# starfire-core.net
KiCad netlist of a schematic drawn in EAGLE
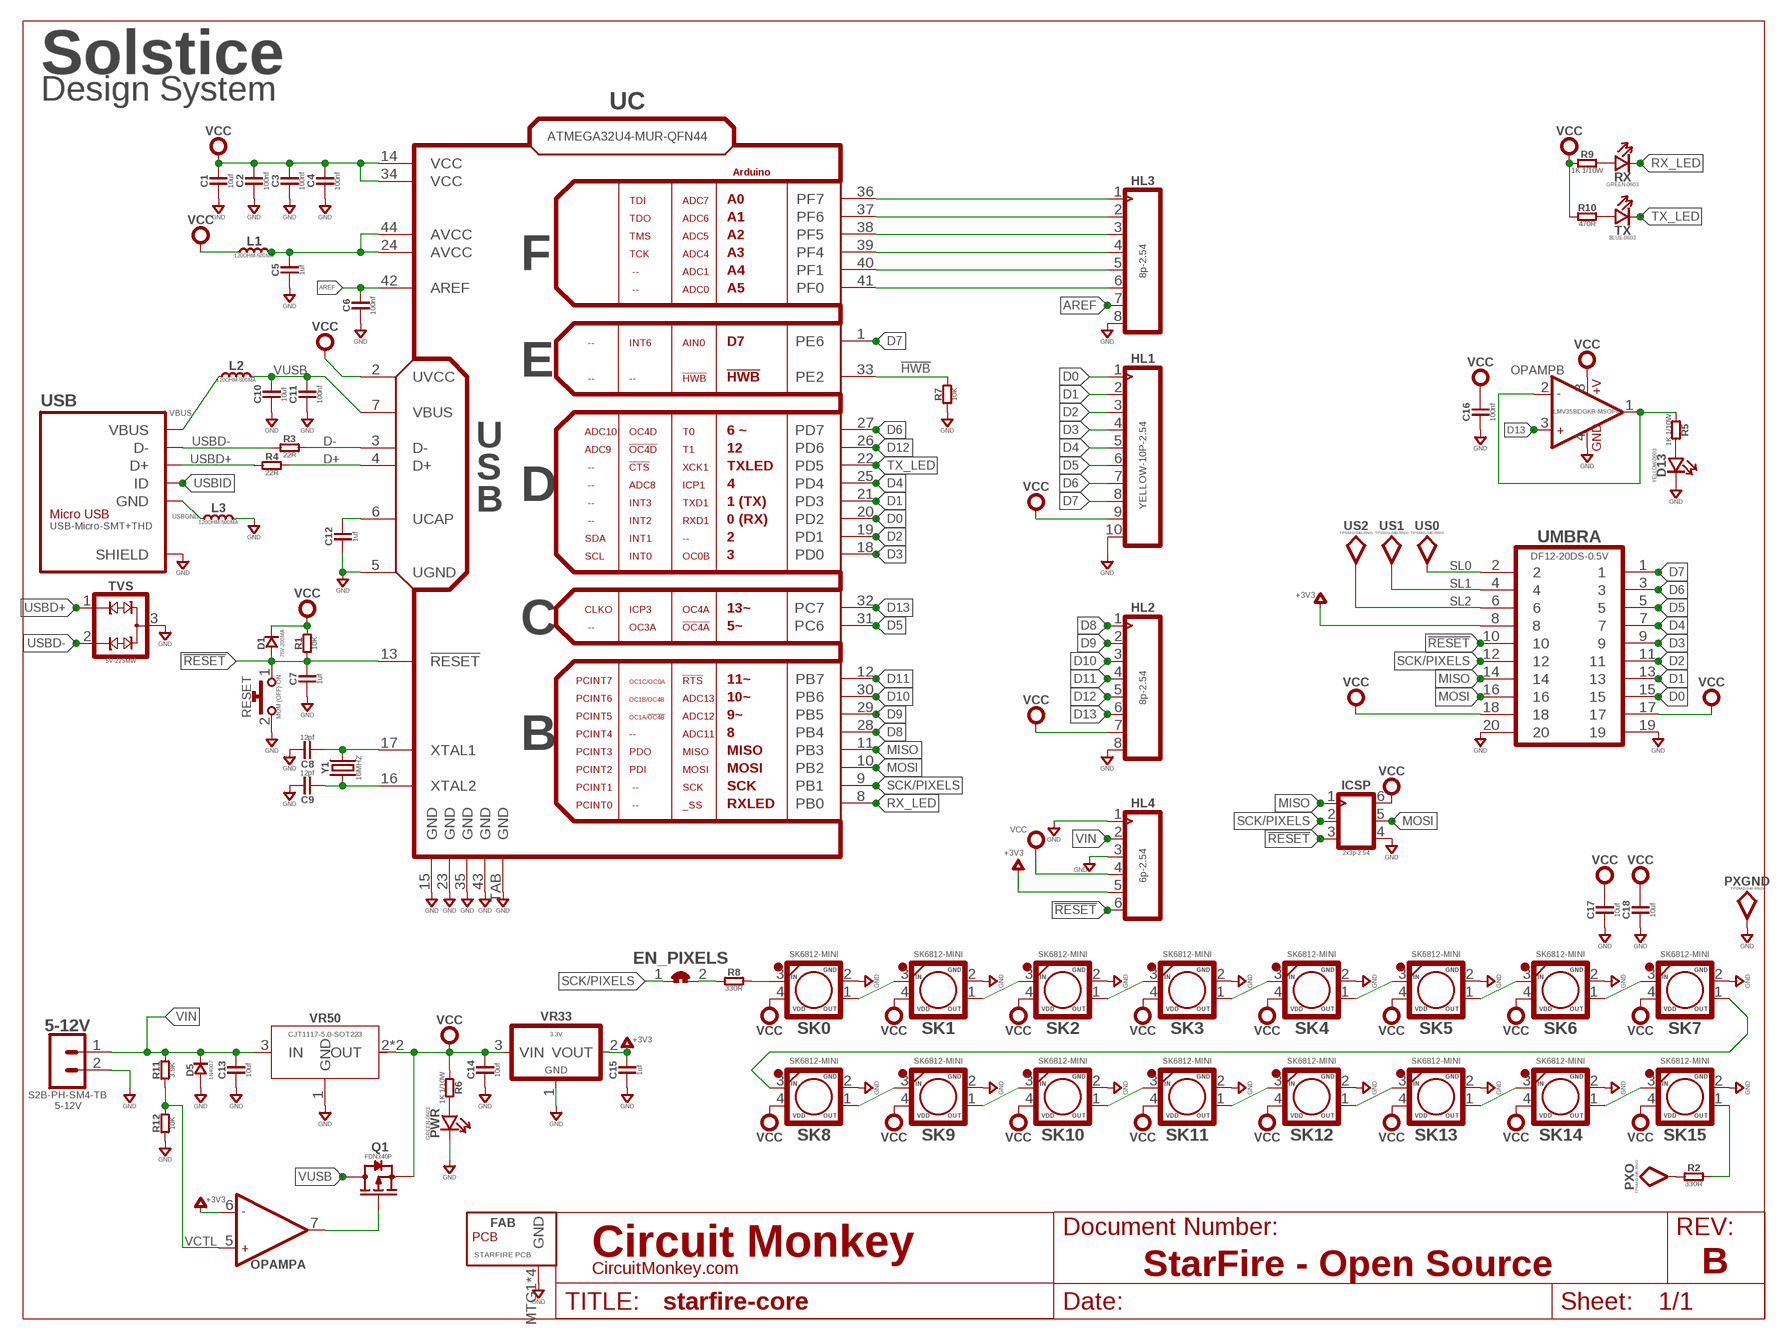
[diagram p0: schematic, sheet 1]

(export (version "E")
  (design (tool "Eeschema 10.0.6"))
  (components
    (comp (ref "5-12V")
      (value "S2B-PH-SM4-TB")
      (footprint "eagle-import:S2B-PH-SM4-")
      (libsource (lib "eagle-import") (part "02PRA-SMT"))
    )
    (comp (ref "C1")
      (value "10uf")
      (footprint "eagle-import:C0603")
      (fields (field (name "MPN") "CC0603KRX5R6BB106"))
      (libsource (lib "eagle-import") (part "CERAMIC-10UF-10V-10%-X5R(0603)"))
    )
    (comp (ref "C2")
      (value "100nf")
      (footprint "eagle-import:C0603")
      (fields (field (name "MPN") "CC0603KRX7R9BB104"))
      (libsource (lib "eagle-import") (part "CERAMIC-100NF-50V-10%-X7R(0603)"))
    )
    (comp (ref "C3")
      (value "100nf")
      (footprint "eagle-import:C0603")
      (fields (field (name "MPN") "CC0603KRX7R9BB104"))
      (libsource (lib "eagle-import") (part "CERAMIC-100NF-50V-10%-X7R(0603)"))
    )
    (comp (ref "C4")
      (value "100nf")
      (footprint "eagle-import:C0603")
      (fields (field (name "MPN") "CC0603KRX7R9BB104"))
      (libsource (lib "eagle-import") (part "CERAMIC-100NF-50V-10%-X7R(0603)"))
    )
    (comp (ref "C5")
      (value "1uf")
      (footprint "eagle-import:C0603")
      (fields (field (name "MPN") "CC0603KRX7R8BB105"))
      (libsource (lib "eagle-import") (part "CERAMIC-1UF-25V-10%-X7R(0603)"))
    )
    (comp (ref "C6")
      (value "100nf")
      (footprint "eagle-import:C0603")
      (fields (field (name "MPN") "CC0603KRX7R9BB104"))
      (libsource (lib "eagle-import") (part "CERAMIC-100NF-50V-10%-X7R(0603)"))
    )
    (comp (ref "C7")
      (value "1uf")
      (footprint "eagle-import:C0603")
      (fields (field (name "MPN") "CC0603KRX7R8BB105"))
      (libsource (lib "eagle-import") (part "CERAMIC-1UF-25V-10%-X7R(0603)"))
    )
    (comp (ref "C8")
      (value "12pf")
      (footprint "eagle-import:C0603")
      (fields (field (name "MPN") "CC0603JRNPO9BN120"))
      (libsource (lib "eagle-import") (part "CERAMIC-12PF-50V-5%-NPO(0603)"))
    )
    (comp (ref "C9")
      (value "12pf")
      (footprint "eagle-import:C0603")
      (fields (field (name "MPN") "CC0603JRNPO9BN120"))
      (libsource (lib "eagle-import") (part "CERAMIC-12PF-50V-5%-NPO(0603)"))
    )
    (comp (ref "C10")
      (value "10uf")
      (footprint "eagle-import:C0603")
      (fields (field (name "MPN") "CC0603KRX5R6BB106"))
      (libsource (lib "eagle-import") (part "CERAMIC-10UF-10V-10%-X5R(0603)"))
    )
    (comp (ref "C11")
      (value "100nf")
      (footprint "eagle-import:C0603")
      (fields (field (name "MPN") "CC0603KRX7R9BB104"))
      (libsource (lib "eagle-import") (part "CERAMIC-100NF-50V-10%-X7R(0603)"))
    )
    (comp (ref "C12")
      (value "1uf")
      (footprint "eagle-import:C0603")
      (fields (field (name "MPN") "CC0603KRX7R8BB105"))
      (libsource (lib "eagle-import") (part "CERAMIC-1UF-25V-10%-X7R(0603)"))
    )
    (comp (ref "C13")
      (value "10uf")
      (footprint "eagle-import:C0603")
      (fields (field (name "MPN") "CC0603KRX5R6BB106"))
      (libsource (lib "eagle-import") (part "CERAMIC-10UF-10V-10%-X5R(0603)"))
    )
    (comp (ref "C14")
      (value "10uf")
      (footprint "eagle-import:C0603")
      (fields (field (name "MPN") "CC0603KRX5R6BB106"))
      (libsource (lib "eagle-import") (part "CERAMIC-10UF-10V-10%-X5R(0603)"))
    )
    (comp (ref "C15")
      (value "1uf")
      (footprint "eagle-import:C0603")
      (fields (field (name "MPN") "CC0603KRX7R8BB105"))
      (libsource (lib "eagle-import") (part "CERAMIC-1UF-25V-10%-X7R(0603)"))
    )
    (comp (ref "C16")
      (value "100nf")
      (footprint "eagle-import:C0603")
      (fields (field (name "MPN") "CC0603KRX7R9BB104"))
      (libsource (lib "eagle-import") (part "CERAMIC-100NF-50V-10%-X7R(0603)"))
    )
    (comp (ref "C17")
      (value "10uf")
      (footprint "eagle-import:C0603")
      (fields (field (name "MPN") "CC0603KRX5R6BB106"))
      (libsource (lib "eagle-import") (part "CERAMIC-10UF-10V-10%-X5R(0603)"))
    )
    (comp (ref "C18")
      (value "10uf")
      (footprint "eagle-import:C0603")
      (fields (field (name "MPN") "CC0603KRX5R6BB106"))
      (libsource (lib "eagle-import") (part "CERAMIC-10UF-10V-10%-X5R(0603)"))
    )
    (comp (ref "D1")
      (value "75V-200MA")
      (footprint "eagle-import:LL-34")
      (fields (field (name "MPN") "LL4148ST"))
      (libsource (lib "eagle-import") (part "SMD-DIODE-SWITCHING-75V-200MA(LL-34)"))
    )
    (comp (ref "D5")
      (value "1N4007")
      (footprint "eagle-import:DO-214AC")
      (libsource (lib "eagle-import") (part "DIODE-GEN-PURPOSE-1KV-1A(DO-214AC)"))
    )
    (comp (ref "D13")
      (value "YELLOW-0603")
      (footprint "eagle-import:LED-0603")
      (fields (field (name "MPN") "19-217-Y5C-AM1N1VY-3T"))
      (libsource (lib "eagle-import") (part "SMD-LED-CLEAR-YELLOW(0603)"))
    )
    (comp (ref "EN_PIXELS")
      (value "SOLDER_JUMPER-80MIL-RND")
      (footprint "eagle-import:SOLDER_JUMP_80MIL_RND")
      (libsource (lib "eagle-import") (part "SOLDER_JUMPER-80MIL-RND"))
    )
    (comp (ref "FAB")
      (value "STARFIRE PCB")
      (footprint "eagle-import:PCB-BASE-B1")
      (libsource (lib "eagle-import") (part "PCB-4-MTG-BASE-B1"))
    )
    (comp (ref "HL1")
      (value "YELLOW-10P-2.54")
      (footprint "eagle-import:H10-2.54")
      (fields (field (name "MPN") "F185-1110A1BSYC1"))
      (libsource (lib "eagle-import") (part "DIP-YELLOW-FEMALE-HEADER-VERT(10P-2.54)"))
    )
    (comp (ref "HL2")
      (value "8p-2.54")
      (footprint "eagle-import:H8-2.54")
      (fields (field (name "MPN") "F185-1108A1BSYC1"))
      (libsource (lib "eagle-import") (part "DIP-BLACK-FEMALE-HEADER-VERT(8P-2.54)"))
    )
    (comp (ref "HL3")
      (value "8p-2.54")
      (footprint "eagle-import:H8-2.54")
      (fields (field (name "MPN") "F185-1108A1BSYC1"))
      (libsource (lib "eagle-import") (part "DIP-BLACK-FEMALE-HEADER-VERT(8P-2.54)"))
    )
    (comp (ref "HL4")
      (value "6p-2.54")
      (footprint "eagle-import:H6-2.54")
      (fields (field (name "MPN") "F185-1106A1BSYC1"))
      (libsource (lib "eagle-import") (part "DIP-BLACK-FEMALE-HEADER-VERT(6P-2.54)"))
    )
    (comp (ref "ICSP")
      (value "2x3p-2.54")
      (footprint "eagle-import:H2X3-2.54")
      (fields (field (name "MPN") "P125-12A1BS116A1"))
      (libsource (lib "eagle-import") (part "DIP-BLACK-MALE-HEADER(2X3P-2.54）-2.54"))
    )
    (comp (ref "L1")
      (value "120OHM-500MA")
      (footprint "eagle-import:L0603")
      (fields (field (name "MPN") "BLM18AG121SN1D"))
      (libsource (lib "eagle-import") (part "SMD-FERRITE-CHIP-120-OHM-500MA(0603)"))
    )
    (comp (ref "L2")
      (value "120OHM-500MA")
      (footprint "eagle-import:L0603")
      (fields (field (name "MPN") "BLM18AG121SN1D"))
      (libsource (lib "eagle-import") (part "SMD-FERRITE-CHIP-120-OHM-500MA(0603)"))
    )
    (comp (ref "L3")
      (value "120OHM-500MA")
      (footprint "eagle-import:L0603")
      (fields (field (name "MPN") "BLM18AG121SN1D"))
      (libsource (lib "eagle-import") (part "SMD-FERRITE-CHIP-120-OHM-500MA(0603)"))
    )
    (comp (ref "OPAMP")
      (value "LMV358IDGKR-MSOP8")
      (footprint "eagle-import:MSOP8-0.65-3X3MM")
      (fields (field (name "MPN") "LMV358IDGKR"))
      (libsource (lib "eagle-import") (part "AMPLIFIER-LMV358IDGKR(MSOP8)"))
    )
    (comp (ref "PWR")
      (value "GREEN-0603")
      (footprint "eagle-import:LED-0603")
      (fields (field (name "MPN") "19-217-G7C-AN1P2-3T"))
      (libsource (lib "eagle-import") (part "SMD-LED-CLEAR-GREEN(0603)"))
    )
    (comp (ref "PXGND")
      (value "TPSMD-040-RND")
      (footprint "eagle-import:SMD-040MIL-RND")
      (libsource (lib "eagle-import") (part "TPSMD-040-RND"))
    )
    (comp (ref "PXO")
      (value "TPSMD-040-RND")
      (footprint "eagle-import:SMD-040MIL-RND")
      (libsource (lib "eagle-import") (part "TPSMD-040-RND"))
    )
    (comp (ref "Q1")
      (value "FDN340P")
      (footprint "eagle-import:SOT-23")
      (libsource (lib "eagle-import") (part "SMD-MOSFET-P-CH-20V-2A-FDN340P(SOT-23)"))
    )
    (comp (ref "R1")
      (value "10K")
      (footprint "eagle-import:R0603")
      (fields (field (name "MPN") "RC0603FR-0710KL"))
      (libsource (lib "eagle-import") (part "SMD-RES-10K-1%-1/10W(0603)"))
    )
    (comp (ref "R2")
      (value "330R")
      (footprint "eagle-import:R0603")
      (fields (field (name "MPN") "RC0603FR-07330RL"))
      (libsource (lib "eagle-import") (part "SMD-RES-330R-1%-1/10W(0603)"))
    )
    (comp (ref "R3")
      (value "22R")
      (footprint "eagle-import:R0603")
      (fields (field (name "MPN") "RC0603JR-0722RL"))
      (libsource (lib "eagle-import") (part "SMD-RES-22R-5%-1/10W(0603)"))
    )
    (comp (ref "R4")
      (value "22R")
      (footprint "eagle-import:R0603")
      (fields (field (name "MPN") "RC0603JR-0722RL"))
      (libsource (lib "eagle-import") (part "SMD-RES-22R-5%-1/10W(0603)"))
    )
    (comp (ref "R5")
      (value "1K 1/10W")
      (footprint "eagle-import:R0603")
      (fields (field (name "MPN") "RC0603JR-071KL"))
      (libsource (lib "eagle-import") (part "SMD-RES-1K-5%-1/10W(0603)"))
    )
    (comp (ref "R6")
      (value "1K 1/10W")
      (footprint "eagle-import:R0603")
      (fields (field (name "MPN") "RC0603JR-071KL"))
      (libsource (lib "eagle-import") (part "SMD-RES-1K-5%-1/10W(0603)"))
    )
    (comp (ref "R7")
      (value "10K")
      (footprint "eagle-import:R0603")
      (fields (field (name "MPN") "RC0603FR-0710KL"))
      (libsource (lib "eagle-import") (part "SMD-RES-10K-1%-1/10W(0603)"))
    )
    (comp (ref "R8")
      (value "330R")
      (footprint "eagle-import:R0603")
      (fields (field (name "MPN") "RC0603FR-07330RL"))
      (libsource (lib "eagle-import") (part "SMD-RES-330R-1%-1/10W(0603)"))
    )
    (comp (ref "R9")
      (value "1K 1/10W")
      (footprint "eagle-import:R0603")
      (fields (field (name "MPN") "RC0603JR-071KL"))
      (libsource (lib "eagle-import") (part "SMD-RES-1K-5%-1/10W(0603)"))
    )
    (comp (ref "R10")
      (value "470R")
      (footprint "eagle-import:R0603")
      (fields (field (name "MPN") "RC0603JR-07470RL"))
      (libsource (lib "eagle-import") (part "SMD-RES-470R-5%-1/10W(0603)"))
    )
    (comp (ref "R11")
      (value "3.9K")
      (footprint "eagle-import:R0603")
      (fields (field (name "MPN") "RC0603JR-073K9L"))
      (libsource (lib "eagle-import") (part "SMD-RES-3.9K-5%-1/10W(0603)"))
    )
    (comp (ref "R12")
      (value "10K")
      (footprint "eagle-import:R0603")
      (fields (field (name "MPN") "RC0603FR-0710KL"))
      (libsource (lib "eagle-import") (part "SMD-RES-10K-1%-1/10W(0603)"))
    )
    (comp (ref "RESET")
      (value "MOM (OFF)-ON")
      (footprint "eagle-import:SWITCH-0635-2P-SMD")
      (fields (field (name "MFR") "CK Switch") (field (name "MPN") "PTS635S*SMTR"))
      (libsource (lib "eagle-import") (part "TACTILE-2PSMD"))
    )
    (comp (ref "RX")
      (value "GREEN-0603")
      (footprint "eagle-import:LED-0603")
      (fields (field (name "MPN") "19-217-G7C-AN1P2-3T"))
      (libsource (lib "eagle-import") (part "SMD-LED-CLEAR-GREEN(0603)"))
    )
    (comp (ref "SK0")
      (value "SK6812-MINI")
      (footprint "eagle-import:SMD_3535")
      (fields (field (name "MFR") "CHINA"))
      (libsource (lib "eagle-import") (part "SK6812MINI"))
    )
    (comp (ref "SK1")
      (value "SK6812-MINI")
      (footprint "eagle-import:SMD_3535")
      (fields (field (name "MFR") "CHINA"))
      (libsource (lib "eagle-import") (part "SK6812MINI"))
    )
    (comp (ref "SK2")
      (value "SK6812-MINI")
      (footprint "eagle-import:SMD_3535")
      (fields (field (name "MFR") "CHINA"))
      (libsource (lib "eagle-import") (part "SK6812MINI"))
    )
    (comp (ref "SK3")
      (value "SK6812-MINI")
      (footprint "eagle-import:SMD_3535")
      (fields (field (name "MFR") "CHINA"))
      (libsource (lib "eagle-import") (part "SK6812MINI"))
    )
    (comp (ref "SK4")
      (value "SK6812-MINI")
      (footprint "eagle-import:SMD_3535")
      (fields (field (name "MFR") "CHINA"))
      (libsource (lib "eagle-import") (part "SK6812MINI"))
    )
    (comp (ref "SK5")
      (value "SK6812-MINI")
      (footprint "eagle-import:SMD_3535")
      (fields (field (name "MFR") "CHINA"))
      (libsource (lib "eagle-import") (part "SK6812MINI"))
    )
    (comp (ref "SK6")
      (value "SK6812-MINI")
      (footprint "eagle-import:SMD_3535")
      (fields (field (name "MFR") "CHINA"))
      (libsource (lib "eagle-import") (part "SK6812MINI"))
    )
    (comp (ref "SK7")
      (value "SK6812-MINI")
      (footprint "eagle-import:SMD_3535")
      (fields (field (name "MFR") "CHINA"))
      (libsource (lib "eagle-import") (part "SK6812MINI"))
    )
    (comp (ref "SK8")
      (value "SK6812-MINI")
      (footprint "eagle-import:SMD_3535")
      (fields (field (name "MFR") "CHINA"))
      (libsource (lib "eagle-import") (part "SK6812MINI"))
    )
    (comp (ref "SK9")
      (value "SK6812-MINI")
      (footprint "eagle-import:SMD_3535")
      (fields (field (name "MFR") "CHINA"))
      (libsource (lib "eagle-import") (part "SK6812MINI"))
    )
    (comp (ref "SK10")
      (value "SK6812-MINI")
      (footprint "eagle-import:SMD_3535")
      (fields (field (name "MFR") "CHINA"))
      (libsource (lib "eagle-import") (part "SK6812MINI"))
    )
    (comp (ref "SK11")
      (value "SK6812-MINI")
      (footprint "eagle-import:SMD_3535")
      (fields (field (name "MFR") "CHINA"))
      (libsource (lib "eagle-import") (part "SK6812MINI"))
    )
    (comp (ref "SK12")
      (value "SK6812-MINI")
      (footprint "eagle-import:SMD_3535")
      (fields (field (name "MFR") "CHINA"))
      (libsource (lib "eagle-import") (part "SK6812MINI"))
    )
    (comp (ref "SK13")
      (value "SK6812-MINI")
      (footprint "eagle-import:SMD_3535")
      (fields (field (name "MFR") "CHINA"))
      (libsource (lib "eagle-import") (part "SK6812MINI"))
    )
    (comp (ref "SK14")
      (value "SK6812-MINI")
      (footprint "eagle-import:SMD_3535")
      (fields (field (name "MFR") "CHINA"))
      (libsource (lib "eagle-import") (part "SK6812MINI"))
    )
    (comp (ref "SK15")
      (value "SK6812-MINI")
      (footprint "eagle-import:SMD_3535")
      (fields (field (name "MFR") "CHINA"))
      (libsource (lib "eagle-import") (part "SK6812MINI"))
    )
    (comp (ref "TVS")
      (value "5V-225MW")
      (footprint "eagle-import:SOT-23")
      (fields (field (name "MPN") "CESD5V0AP"))
      (libsource (lib "eagle-import") (part "SMD-DIODE-TVS-5V-225MW(SOT-23)"))
    )
    (comp (ref "TX")
      (value "BLUE-0603")
      (footprint "eagle-import:LED-0603")
      (fields (field (name "MPN") "19-217-BHC-ZL1M2RY-3T"))
      (libsource (lib "eagle-import") (part "SMD-LED-CLEAR-BLUE(0603)"))
    )
    (comp (ref "UC")
      (value "ATMEGA32U4-MUR-QFN44")
      (footprint "eagle-import:QFN44G-0.5-7X7MM")
      (fields (field (name "MPN") "ATMEGA32U4-MUR"))
      (libsource (lib "eagle-import") (part "MCU-ATMEGA32U4-MUR(VQFN44)"))
    )
    (comp (ref "UMBRA")
      (value "DF12-20DS-0.5V")
      (footprint "eagle-import:DF12-20P-RCPT-MTL-BOSS")
      (libsource (lib "eagle-import") (part "DF12-20P-RCPT"))
    )
    (comp (ref "US0")
      (value "TPSMD-040-RND")
      (footprint "eagle-import:SMD-040MIL-RND")
      (libsource (lib "eagle-import") (part "TPSMD-040-RND"))
    )
    (comp (ref "US1")
      (value "TPSMD-040-RND")
      (footprint "eagle-import:SMD-040MIL-RND")
      (libsource (lib "eagle-import") (part "TPSMD-040-RND"))
    )
    (comp (ref "US2")
      (value "TPSMD-040-RND")
      (footprint "eagle-import:SMD-040MIL-RND")
      (libsource (lib "eagle-import") (part "TPSMD-040-RND"))
    )
    (comp (ref "USB")
      (value "USB-Micro-SMT+THD")
      (footprint "eagle-import:MICRO-USB5+6P-SMD-0.65-AB")
      (fields (field (name "MPN") "ZX62-B-5PA8"))
      (libsource (lib "eagle-import") (part "MICRO-USB-SMD(ZX62-B-5PA)"))
    )
    (comp (ref "VR33")
      (value "3.3V")
      (footprint "eagle-import:SOT-23")
      (fields (field (name "MPN") "XC6206P332MR-G"))
      (libsource (lib "eagle-import") (part "PMIC-LDO-XC6206P332MR-G(SOT23)"))
    )
    (comp (ref "VR50")
      (value "CJT1117-5.0-SOT223")
      (footprint "eagle-import:SOT-223")
      (fields (field (name "MPN") "CJT1117-5.0"))
      (libsource (lib "eagle-import") (part "PMIC-CJT1117-5.0(SOT223)"))
    )
    (comp (ref "Y1")
      (value "16MHZ")
      (footprint "eagle-import:X2-SMD-5.0X3.2X1.3MM")
      (fields (field (name "MPN") "X053201602002"))
      (libsource (lib "eagle-import") (part "SMD-CRYSTAL-16MHZ-8PF-20PPM-40R(2P-5.0X3.2MM)"))
    )
  )
  (nets
    (net (code "1") (name "+3V3") (class "Default")
      (node (ref "C15") (pin "2") (pinfunction "2_2") (pintype "passive"))
      (node (ref "HL4") (pin "5") (pinfunction "5_5") (pintype "bidirectional"))
      (node (ref "OPAMP") (pin "6") (pinfunction "-IN2_6") (pintype "input"))
      (node (ref "UMBRA") (pin "8") (pinfunction "8_8") (pintype "bidirectional"))
      (node (ref "VR33") (pin "2") (pinfunction "VOUT_2") (pintype "output"))
    )
    (net (code "2") (name "/D+") (class "Default")
      (node (ref "R4") (pin "2") (pinfunction "2_2") (pintype "passive"))
      (node (ref "UC") (pin "4") (pinfunction "D+_4") (pintype "bidirectional"))
    )
    (net (code "3") (name "/D-") (class "Default")
      (node (ref "R3") (pin "2") (pinfunction "2_2") (pintype "passive"))
      (node (ref "UC") (pin "3") (pinfunction "D-_3") (pintype "bidirectional"))
    )
    (net (code "4") (name "/SL0") (class "Default")
      (node (ref "UMBRA") (pin "2") (pinfunction "2_2") (pintype "bidirectional"))
      (node (ref "US0") (pin "TP") (pinfunction "P$1_TP") (pintype "bidirectional"))
    )
    (net (code "5") (name "/SL1") (class "Default")
      (node (ref "UMBRA") (pin "4") (pinfunction "4_4") (pintype "bidirectional"))
      (node (ref "US1") (pin "TP") (pinfunction "P$1_TP") (pintype "bidirectional"))
    )
    (net (code "6") (name "/SL2") (class "Default")
      (node (ref "UMBRA") (pin "6") (pinfunction "6_6") (pintype "bidirectional"))
      (node (ref "US2") (pin "TP") (pinfunction "P$1_TP") (pintype "bidirectional"))
    )
    (net (code "7") (name "/USBGND") (class "Default")
      (node (ref "L3") (pin "1") (pinfunction "1_1") (pintype "passive"))
      (node (ref "USB") (pin "5") (pinfunction "GND_5") (pintype "power_in"))
    )
    (net (code "8") (name "/VBUS") (class "Default")
      (node (ref "L2") (pin "1") (pinfunction "1_1") (pintype "passive"))
      (node (ref "USB") (pin "1") (pinfunction "VBUS_1") (pintype "power_in"))
    )
    (net (code "9") (name "/VCTL") (class "Default")
      (node (ref "OPAMP") (pin "5") (pinfunction "+IN2_5") (pintype "input"))
      (node (ref "R11") (pin "1") (pinfunction "1_1") (pintype "passive"))
      (node (ref "R12") (pin "2") (pinfunction "2_2") (pintype "passive"))
    )
    (net (code "10") (name "/~{HWB}") (class "Default")
      (node (ref "R7") (pin "2") (pinfunction "2_2") (pintype "passive"))
      (node (ref "UC") (pin "33") (pinfunction "PE2_33") (pintype "bidirectional"))
    )
    (net (code "11") (name "/~{RESET}") (class "Default")
      (node (ref "C7") (pin "2") (pinfunction "2_2") (pintype "passive"))
      (node (ref "D1") (pin "A") (pinfunction "+_A") (pintype "passive"))
      (node (ref "HL4") (pin "6") (pinfunction "6_6") (pintype "bidirectional"))
      (node (ref "ICSP") (pin "3") (pinfunction "3_3") (pintype "bidirectional"))
      (node (ref "R1") (pin "1") (pinfunction "1_1") (pintype "passive"))
      (node (ref "RESET") (pin "1") (pinfunction "1_1") (pintype "bidirectional"))
      (node (ref "UC") (pin "13") (pinfunction "~{RESET}_13") (pintype "input"))
      (node (ref "UMBRA") (pin "10") (pinfunction "10_10") (pintype "bidirectional"))
    )
    (net (code "12") (name "AREF") (class "Default")
      (node (ref "C6") (pin "2") (pinfunction "2_2") (pintype "passive"))
      (node (ref "HL3") (pin "7") (pinfunction "7_7") (pintype "bidirectional"))
      (node (ref "UC") (pin "42") (pinfunction "AREF_42") (pintype "input"))
    )
    (net (code "13") (name "D0") (class "Default")
      (node (ref "HL1") (pin "1") (pinfunction "1_1") (pintype "bidirectional"))
      (node (ref "UC") (pin "20") (pinfunction "PD2_20") (pintype "bidirectional"))
      (node (ref "UMBRA") (pin "15") (pinfunction "15_15") (pintype "bidirectional"))
    )
    (net (code "14") (name "D1") (class "Default")
      (node (ref "HL1") (pin "2") (pinfunction "2_2") (pintype "bidirectional"))
      (node (ref "UC") (pin "21") (pinfunction "PD3_21") (pintype "bidirectional"))
      (node (ref "UMBRA") (pin "13") (pinfunction "13_13") (pintype "bidirectional"))
    )
    (net (code "15") (name "D2") (class "Default")
      (node (ref "HL1") (pin "3") (pinfunction "3_3") (pintype "bidirectional"))
      (node (ref "UC") (pin "19") (pinfunction "PD1_19") (pintype "bidirectional"))
      (node (ref "UMBRA") (pin "11") (pinfunction "11_11") (pintype "bidirectional"))
    )
    (net (code "16") (name "D3") (class "Default")
      (node (ref "HL1") (pin "4") (pinfunction "4_4") (pintype "bidirectional"))
      (node (ref "UC") (pin "18") (pinfunction "PD0_18") (pintype "bidirectional"))
      (node (ref "UMBRA") (pin "9") (pinfunction "9_9") (pintype "bidirectional"))
    )
    (net (code "17") (name "D4") (class "Default")
      (node (ref "HL1") (pin "5") (pinfunction "5_5") (pintype "bidirectional"))
      (node (ref "UC") (pin "25") (pinfunction "PD4_25") (pintype "bidirectional"))
      (node (ref "UMBRA") (pin "7") (pinfunction "7_7") (pintype "bidirectional"))
    )
    (net (code "18") (name "D5") (class "Default")
      (node (ref "HL1") (pin "6") (pinfunction "6_6") (pintype "bidirectional"))
      (node (ref "UC") (pin "31") (pinfunction "PC6_31") (pintype "bidirectional"))
      (node (ref "UMBRA") (pin "5") (pinfunction "5_5") (pintype "bidirectional"))
    )
    (net (code "19") (name "D6") (class "Default")
      (node (ref "HL1") (pin "7") (pinfunction "7_7") (pintype "bidirectional"))
      (node (ref "UC") (pin "27") (pinfunction "PD7_27") (pintype "bidirectional"))
      (node (ref "UMBRA") (pin "3") (pinfunction "3_3") (pintype "bidirectional"))
    )
    (net (code "20") (name "D7") (class "Default")
      (node (ref "HL1") (pin "8") (pinfunction "8_8") (pintype "bidirectional"))
      (node (ref "UC") (pin "1") (pinfunction "PE6_1") (pintype "bidirectional"))
      (node (ref "UMBRA") (pin "1") (pinfunction "1_1") (pintype "bidirectional"))
    )
    (net (code "21") (name "D8") (class "Default")
      (node (ref "HL2") (pin "1") (pinfunction "1_1") (pintype "bidirectional"))
      (node (ref "UC") (pin "28") (pinfunction "PB4_28") (pintype "bidirectional"))
    )
    (net (code "22") (name "D9") (class "Default")
      (node (ref "HL2") (pin "2") (pinfunction "2_2") (pintype "bidirectional"))
      (node (ref "UC") (pin "29") (pinfunction "PB5_29") (pintype "bidirectional"))
    )
    (net (code "23") (name "D10") (class "Default")
      (node (ref "HL2") (pin "3") (pinfunction "3_3") (pintype "bidirectional"))
      (node (ref "UC") (pin "30") (pinfunction "PB6_30") (pintype "bidirectional"))
    )
    (net (code "24") (name "D11") (class "Default")
      (node (ref "HL2") (pin "4") (pinfunction "4_4") (pintype "bidirectional"))
      (node (ref "UC") (pin "12") (pinfunction "PB7_12") (pintype "bidirectional"))
    )
    (net (code "25") (name "D12") (class "Default")
      (node (ref "HL2") (pin "5") (pinfunction "5_5") (pintype "bidirectional"))
      (node (ref "UC") (pin "26") (pinfunction "PD6_26") (pintype "bidirectional"))
    )
    (net (code "26") (name "D13") (class "Default")
      (node (ref "HL2") (pin "6") (pinfunction "6_6") (pintype "bidirectional"))
      (node (ref "OPAMP") (pin "3") (pinfunction "+IN1_3") (pintype "input"))
      (node (ref "UC") (pin "32") (pinfunction "PC7_32") (pintype "bidirectional"))
    )
    (net (code "27") (name "GND") (class "Default")
      (node (ref "5-12V") (pin "2") (pinfunction "2_2") (pintype "passive"))
      (node (ref "C1") (pin "1") (pinfunction "1_1") (pintype "passive"))
      (node (ref "C10") (pin "1") (pinfunction "1_1") (pintype "passive"))
      (node (ref "C11") (pin "1") (pinfunction "1_1") (pintype "passive"))
      (node (ref "C12") (pin "1") (pinfunction "1_1") (pintype "passive"))
      (node (ref "C13") (pin "1") (pinfunction "1_1") (pintype "passive"))
      (node (ref "C14") (pin "1") (pinfunction "1_1") (pintype "passive"))
      (node (ref "C15") (pin "1") (pinfunction "1_1") (pintype "passive"))
      (node (ref "C16") (pin "1") (pinfunction "1_1") (pintype "passive"))
      (node (ref "C17") (pin "1") (pinfunction "1_1") (pintype "passive"))
      (node (ref "C18") (pin "1") (pinfunction "1_1") (pintype "passive"))
      (node (ref "C2") (pin "1") (pinfunction "1_1") (pintype "passive"))
      (node (ref "C3") (pin "1") (pinfunction "1_1") (pintype "passive"))
      (node (ref "C4") (pin "1") (pinfunction "1_1") (pintype "passive"))
      (node (ref "C5") (pin "1") (pinfunction "1_1") (pintype "passive"))
      (node (ref "C6") (pin "1") (pinfunction "1_1") (pintype "passive"))
      (node (ref "C7") (pin "1") (pinfunction "1_1") (pintype "passive"))
      (node (ref "C8") (pin "2") (pinfunction "2_2") (pintype "passive"))
      (node (ref "C9") (pin "2") (pinfunction "2_2") (pintype "passive"))
      (node (ref "D13") (pin "-") (pinfunction "-_-") (pintype "passive"))
      (node (ref "D5") (pin "1") (pinfunction "+_1") (pintype "passive"))
      (node (ref "FAB") (pin "MTG1") (pinfunction "GND_MTG1") (pintype "bidirectional"))
      (node (ref "FAB") (pin "MTG2") (pinfunction "GND_MTG2") (pintype "bidirectional"))
      (node (ref "FAB") (pin "MTG3") (pinfunction "GND_MTG3") (pintype "bidirectional"))
      (node (ref "FAB") (pin "MTG4") (pinfunction "GND_MTG4") (pintype "bidirectional"))
      (node (ref "HL1") (pin "10") (pinfunction "10_10") (pintype "bidirectional"))
      (node (ref "HL2") (pin "8") (pinfunction "8_8") (pintype "bidirectional"))
      (node (ref "HL3") (pin "8") (pinfunction "8_8") (pintype "bidirectional"))
      (node (ref "HL4") (pin "1") (pinfunction "1_1") (pintype "bidirectional"))
      (node (ref "HL4") (pin "3") (pinfunction "3_3") (pintype "bidirectional"))
      (node (ref "ICSP") (pin "4") (pinfunction "4_4") (pintype "bidirectional"))
      (node (ref "L3") (pin "2") (pinfunction "2_2") (pintype "passive"))
      (node (ref "OPAMP") (pin "4") (pinfunction "GND_4") (pintype "power_in"))
      (node (ref "PWR") (pin "-") (pinfunction "-_-") (pintype "passive"))
      (node (ref "PXGND") (pin "TP") (pinfunction "P$1_TP") (pintype "bidirectional"))
      (node (ref "R12") (pin "1") (pinfunction "1_1") (pintype "passive"))
      (node (ref "R7") (pin "1") (pinfunction "1_1") (pintype "passive"))
      (node (ref "RESET") (pin "2") (pinfunction "2_2") (pintype "bidirectional"))
      (node (ref "SK0") (pin "2") (pinfunction "GND_2") (pintype "bidirectional"))
      (node (ref "SK1") (pin "2") (pinfunction "GND_2") (pintype "bidirectional"))
      (node (ref "SK10") (pin "2") (pinfunction "GND_2") (pintype "bidirectional"))
      (node (ref "SK11") (pin "2") (pinfunction "GND_2") (pintype "bidirectional"))
      (node (ref "SK12") (pin "2") (pinfunction "GND_2") (pintype "bidirectional"))
      (node (ref "SK13") (pin "2") (pinfunction "GND_2") (pintype "bidirectional"))
      (node (ref "SK14") (pin "2") (pinfunction "GND_2") (pintype "bidirectional"))
      (node (ref "SK15") (pin "2") (pinfunction "GND_2") (pintype "bidirectional"))
      (node (ref "SK2") (pin "2") (pinfunction "GND_2") (pintype "bidirectional"))
      (node (ref "SK3") (pin "2") (pinfunction "GND_2") (pintype "bidirectional"))
      (node (ref "SK4") (pin "2") (pinfunction "GND_2") (pintype "bidirectional"))
      (node (ref "SK5") (pin "2") (pinfunction "GND_2") (pintype "bidirectional"))
      (node (ref "SK6") (pin "2") (pinfunction "GND_2") (pintype "bidirectional"))
      (node (ref "SK7") (pin "2") (pinfunction "GND_2") (pintype "bidirectional"))
      (node (ref "SK8") (pin "2") (pinfunction "GND_2") (pintype "bidirectional"))
      (node (ref "SK9") (pin "2") (pinfunction "GND_2") (pintype "bidirectional"))
      (node (ref "TVS") (pin "3") (pinfunction "3_3") (pintype "bidirectional"))
      (node (ref "UC") (pin "15") (pinfunction "GND_15") (pintype "power_in"))
      (node (ref "UC") (pin "23") (pinfunction "GND_23") (pintype "power_in"))
      (node (ref "UC") (pin "35") (pinfunction "GND_35") (pintype "power_in"))
      (node (ref "UC") (pin "43") (pinfunction "GND_43") (pintype "power_in"))
      (node (ref "UC") (pin "5") (pinfunction "UGND_5") (pintype "bidirectional"))
      (node (ref "UC") (pin "TAB") (pinfunction "GND_TAB") (pintype "power_in"))
      (node (ref "UMBRA") (pin "19") (pinfunction "19_19") (pintype "bidirectional"))
      (node (ref "UMBRA") (pin "20") (pinfunction "20_20") (pintype "bidirectional"))
      (node (ref "USB") (pin "P1") (pinfunction "SHIELD_P1") (pintype "power_in"))
      (node (ref "USB") (pin "P2") (pinfunction "SHIELD_P2") (pintype "power_in"))
      (node (ref "USB") (pin "P3_1") (pinfunction "SHIELD_P3_1") (pintype "power_in"))
      (node (ref "USB") (pin "P3_2") (pinfunction "SHIELD_P3_2") (pintype "power_in"))
      (node (ref "USB") (pin "P3_3") (pinfunction "SHIELD_P3_3") (pintype "power_in"))
      (node (ref "USB") (pin "P4_1") (pinfunction "SHIELD_P4_1") (pintype "power_in"))
      (node (ref "USB") (pin "P4_2") (pinfunction "SHIELD_P4_2") (pintype "power_in"))
      (node (ref "USB") (pin "P4_3") (pinfunction "SHIELD_P4_3") (pintype "power_in"))
      (node (ref "USB") (pin "P5") (pinfunction "SHIELD_P5") (pintype "power_in"))
      (node (ref "USB") (pin "P6") (pinfunction "SHIELD_P6") (pintype "power_in"))
      (node (ref "VR33") (pin "1") (pinfunction "VSS_1") (pintype "power_in"))
      (node (ref "VR50") (pin "1") (pinfunction "GND_1") (pintype "bidirectional"))
    )
    (net (code "28") (name "MISO") (class "Default")
      (node (ref "ICSP") (pin "1") (pinfunction "1_1") (pintype "bidirectional"))
      (node (ref "UC") (pin "11") (pinfunction "PB3_11") (pintype "bidirectional"))
      (node (ref "UMBRA") (pin "14") (pinfunction "14_14") (pintype "bidirectional"))
    )
    (net (code "29") (name "MOSI") (class "Default")
      (node (ref "ICSP") (pin "5") (pinfunction "5_5") (pintype "bidirectional"))
      (node (ref "UC") (pin "10") (pinfunction "PB2_10") (pintype "bidirectional"))
      (node (ref "UMBRA") (pin "16") (pinfunction "16_16") (pintype "bidirectional"))
    )
    (net (code "30") (name "Net-(C5-Pad2)") (class "Default")
      (node (ref "C5") (pin "2") (pinfunction "2_2") (pintype "passive"))
      (node (ref "L1") (pin "2") (pinfunction "2_2") (pintype "passive"))
      (node (ref "UC") (pin "24") (pinfunction "AVCC_24") (pintype "power_in"))
      (node (ref "UC") (pin "44") (pinfunction "AVCC_44") (pintype "power_in"))
    )
    (net (code "31") (name "Net-(D13-Pad+)") (class "Default")
      (node (ref "D13") (pin "+") (pinfunction "+_+") (pintype "passive"))
      (node (ref "R5") (pin "2") (pinfunction "2_2") (pintype "passive"))
    )
    (net (code "32") (name "Net-(EN_PIXELS-P$2)") (class "Default")
      (node (ref "EN_PIXELS") (pin "2") (pinfunction "P$2_2") (pintype "passive"))
      (node (ref "R8") (pin "1") (pinfunction "1_1") (pintype "passive"))
    )
    (net (code "33") (name "Net-(OPAMPA-OUT2)") (class "Default")
      (node (ref "OPAMP") (pin "7") (pinfunction "OUT2_7") (pintype "output"))
      (node (ref "Q1") (pin "1") (pinfunction "G_1") (pintype "passive"))
    )
    (net (code "34") (name "Net-(OPAMPB--IN1)") (class "Default")
      (node (ref "OPAMP") (pin "1") (pinfunction "OUT1_1") (pintype "output"))
      (node (ref "OPAMP") (pin "2") (pinfunction "-IN1_2") (pintype "input"))
      (node (ref "R5") (pin "1") (pinfunction "1_1") (pintype "passive"))
    )
    (net (code "35") (name "Net-(PWR-Pad+)") (class "Default")
      (node (ref "PWR") (pin "+") (pinfunction "+_+") (pintype "passive"))
      (node (ref "R6") (pin "2") (pinfunction "2_2") (pintype "passive"))
    )
    (net (code "36") (name "Net-(PXO-P$1)") (class "Default")
      (node (ref "PXO") (pin "TP") (pinfunction "P$1_TP") (pintype "bidirectional"))
      (node (ref "R2") (pin "1") (pinfunction "1_1") (pintype "passive"))
    )
    (net (code "37") (name "Net-(R9-Pad2)") (class "Default")
      (node (ref "R9") (pin "2") (pinfunction "2_2") (pintype "passive"))
      (node (ref "RX") (pin "+") (pinfunction "+_+") (pintype "passive"))
    )
    (net (code "38") (name "Net-(R10-Pad2)") (class "Default")
      (node (ref "R10") (pin "2") (pinfunction "2_2") (pintype "passive"))
      (node (ref "TX") (pin "+") (pinfunction "+_+") (pintype "passive"))
    )
    (net (code "39") (name "Net-(SK0-IN)") (class "Default")
      (node (ref "R8") (pin "2") (pinfunction "2_2") (pintype "passive"))
      (node (ref "SK0") (pin "3") (pinfunction "IN_3") (pintype "bidirectional"))
    )
    (net (code "40") (name "Net-(SK0-OUT)") (class "Default")
      (node (ref "SK0") (pin "1") (pinfunction "OUT_1") (pintype "bidirectional"))
      (node (ref "SK1") (pin "3") (pinfunction "IN_3") (pintype "bidirectional"))
    )
    (net (code "41") (name "Net-(SK1-OUT)") (class "Default")
      (node (ref "SK1") (pin "1") (pinfunction "OUT_1") (pintype "bidirectional"))
      (node (ref "SK2") (pin "3") (pinfunction "IN_3") (pintype "bidirectional"))
    )
    (net (code "42") (name "Net-(SK2-OUT)") (class "Default")
      (node (ref "SK2") (pin "1") (pinfunction "OUT_1") (pintype "bidirectional"))
      (node (ref "SK3") (pin "3") (pinfunction "IN_3") (pintype "bidirectional"))
    )
    (net (code "43") (name "Net-(SK3-OUT)") (class "Default")
      (node (ref "SK3") (pin "1") (pinfunction "OUT_1") (pintype "bidirectional"))
      (node (ref "SK4") (pin "3") (pinfunction "IN_3") (pintype "bidirectional"))
    )
    (net (code "44") (name "Net-(SK4-OUT)") (class "Default")
      (node (ref "SK4") (pin "1") (pinfunction "OUT_1") (pintype "bidirectional"))
      (node (ref "SK5") (pin "3") (pinfunction "IN_3") (pintype "bidirectional"))
    )
    (net (code "45") (name "Net-(SK5-OUT)") (class "Default")
      (node (ref "SK5") (pin "1") (pinfunction "OUT_1") (pintype "bidirectional"))
      (node (ref "SK6") (pin "3") (pinfunction "IN_3") (pintype "bidirectional"))
    )
    (net (code "46") (name "Net-(SK6-OUT)") (class "Default")
      (node (ref "SK6") (pin "1") (pinfunction "OUT_1") (pintype "bidirectional"))
      (node (ref "SK7") (pin "3") (pinfunction "IN_3") (pintype "bidirectional"))
    )
    (net (code "47") (name "Net-(SK7-OUT)") (class "Default")
      (node (ref "SK7") (pin "1") (pinfunction "OUT_1") (pintype "bidirectional"))
      (node (ref "SK8") (pin "3") (pinfunction "IN_3") (pintype "bidirectional"))
    )
    (net (code "48") (name "Net-(SK8-OUT)") (class "Default")
      (node (ref "SK8") (pin "1") (pinfunction "OUT_1") (pintype "bidirectional"))
      (node (ref "SK9") (pin "3") (pinfunction "IN_3") (pintype "bidirectional"))
    )
    (net (code "49") (name "Net-(SK10-IN)") (class "Default")
      (node (ref "SK10") (pin "3") (pinfunction "IN_3") (pintype "bidirectional"))
      (node (ref "SK9") (pin "1") (pinfunction "OUT_1") (pintype "bidirectional"))
    )
    (net (code "50") (name "Net-(SK10-OUT)") (class "Default")
      (node (ref "SK10") (pin "1") (pinfunction "OUT_1") (pintype "bidirectional"))
      (node (ref "SK11") (pin "3") (pinfunction "IN_3") (pintype "bidirectional"))
    )
    (net (code "51") (name "Net-(SK11-OUT)") (class "Default")
      (node (ref "SK11") (pin "1") (pinfunction "OUT_1") (pintype "bidirectional"))
      (node (ref "SK12") (pin "3") (pinfunction "IN_3") (pintype "bidirectional"))
    )
    (net (code "52") (name "Net-(SK12-OUT)") (class "Default")
      (node (ref "SK12") (pin "1") (pinfunction "OUT_1") (pintype "bidirectional"))
      (node (ref "SK13") (pin "3") (pinfunction "IN_3") (pintype "bidirectional"))
    )
    (net (code "53") (name "Net-(SK13-OUT)") (class "Default")
      (node (ref "SK13") (pin "1") (pinfunction "OUT_1") (pintype "bidirectional"))
      (node (ref "SK14") (pin "3") (pinfunction "IN_3") (pintype "bidirectional"))
    )
    (net (code "54") (name "Net-(SK14-OUT)") (class "Default")
      (node (ref "SK14") (pin "1") (pinfunction "OUT_1") (pintype "bidirectional"))
      (node (ref "SK15") (pin "3") (pinfunction "IN_3") (pintype "bidirectional"))
    )
    (net (code "55") (name "Net-(SK15-OUT)") (class "Default")
      (node (ref "R2") (pin "2") (pinfunction "2_2") (pintype "passive"))
      (node (ref "SK15") (pin "1") (pinfunction "OUT_1") (pintype "bidirectional"))
    )
    (net (code "56") (name "Net-(UC-PF0)") (class "Default")
      (node (ref "HL3") (pin "6") (pinfunction "6_6") (pintype "bidirectional"))
      (node (ref "UC") (pin "41") (pinfunction "PF0_41") (pintype "bidirectional"))
    )
    (net (code "57") (name "Net-(UC-PF1)") (class "Default")
      (node (ref "HL3") (pin "5") (pinfunction "5_5") (pintype "bidirectional"))
      (node (ref "UC") (pin "40") (pinfunction "PF1_40") (pintype "bidirectional"))
    )
    (net (code "58") (name "Net-(UC-PF4)") (class "Default")
      (node (ref "HL3") (pin "4") (pinfunction "4_4") (pintype "bidirectional"))
      (node (ref "UC") (pin "39") (pinfunction "PF4_39") (pintype "bidirectional"))
    )
    (net (code "59") (name "Net-(UC-PF5)") (class "Default")
      (node (ref "HL3") (pin "3") (pinfunction "3_3") (pintype "bidirectional"))
      (node (ref "UC") (pin "38") (pinfunction "PF5_38") (pintype "bidirectional"))
    )
    (net (code "60") (name "Net-(UC-PF6)") (class "Default")
      (node (ref "HL3") (pin "2") (pinfunction "2_2") (pintype "bidirectional"))
      (node (ref "UC") (pin "37") (pinfunction "PF6_37") (pintype "bidirectional"))
    )
    (net (code "61") (name "Net-(UC-PF7)") (class "Default")
      (node (ref "HL3") (pin "1") (pinfunction "1_1") (pintype "bidirectional"))
      (node (ref "UC") (pin "36") (pinfunction "PF7_36") (pintype "bidirectional"))
    )
    (net (code "62") (name "Net-(UC-UCAP)") (class "Default")
      (node (ref "C12") (pin "2") (pinfunction "2_2") (pintype "passive"))
      (node (ref "UC") (pin "6") (pinfunction "UCAP_6") (pintype "passive"))
    )
    (net (code "63") (name "Net-(UC-XTAL1)") (class "Default")
      (node (ref "C8") (pin "1") (pinfunction "1_1") (pintype "passive"))
      (node (ref "UC") (pin "17") (pinfunction "XTAL1_17") (pintype "passive"))
      (node (ref "Y1") (pin "2") (pinfunction "2_2") (pintype "passive"))
    )
    (net (code "64") (name "Net-(UC-XTAL2)") (class "Default")
      (node (ref "C9") (pin "1") (pinfunction "1_1") (pintype "passive"))
      (node (ref "UC") (pin "16") (pinfunction "XTAL2_16") (pintype "passive"))
      (node (ref "Y1") (pin "1") (pinfunction "1_1") (pintype "passive"))
    )
    (net (code "65") (name "RX_LED") (class "Default")
      (node (ref "RX") (pin "-") (pinfunction "-_-") (pintype "passive"))
      (node (ref "UC") (pin "8") (pinfunction "PB0_8") (pintype "bidirectional"))
    )
    (net (code "66") (name "SCK{slash}PIXELS") (class "Default")
      (node (ref "EN_PIXELS") (pin "1") (pinfunction "P$1_1") (pintype "passive"))
      (node (ref "ICSP") (pin "2") (pinfunction "2_2") (pintype "bidirectional"))
      (node (ref "UC") (pin "9") (pinfunction "PB1_9") (pintype "bidirectional"))
      (node (ref "UMBRA") (pin "12") (pinfunction "12_12") (pintype "bidirectional"))
    )
    (net (code "67") (name "TX_LED") (class "Default")
      (node (ref "TX") (pin "-") (pinfunction "-_-") (pintype "passive"))
      (node (ref "UC") (pin "22") (pinfunction "PD5_22") (pintype "bidirectional"))
    )
    (net (code "68") (name "USBD+") (class "Default")
      (node (ref "R4") (pin "1") (pinfunction "1_1") (pintype "passive"))
      (node (ref "TVS") (pin "1") (pinfunction "1_1") (pintype "bidirectional"))
      (node (ref "USB") (pin "3") (pinfunction "D+_3") (pintype "bidirectional"))
    )
    (net (code "69") (name "USBD-") (class "Default")
      (node (ref "R3") (pin "1") (pinfunction "1_1") (pintype "passive"))
      (node (ref "TVS") (pin "2") (pinfunction "2_2") (pintype "bidirectional"))
      (node (ref "USB") (pin "2") (pinfunction "D-_2") (pintype "bidirectional"))
    )
    (net (code "70") (name "USBID") (class "Default")
      (node (ref "USB") (pin "4") (pinfunction "ID_4") (pintype "bidirectional"))
    )
    (net (code "71") (name "VCC") (class "Default")
      (node (ref "C1") (pin "2") (pinfunction "2_2") (pintype "passive"))
      (node (ref "C14") (pin "2") (pinfunction "2_2") (pintype "passive"))
      (node (ref "C16") (pin "2") (pinfunction "2_2") (pintype "passive"))
      (node (ref "C17") (pin "2") (pinfunction "2_2") (pintype "passive"))
      (node (ref "C18") (pin "2") (pinfunction "2_2") (pintype "passive"))
      (node (ref "C2") (pin "2") (pinfunction "2_2") (pintype "passive"))
      (node (ref "C3") (pin "2") (pinfunction "2_2") (pintype "passive"))
      (node (ref "C4") (pin "2") (pinfunction "2_2") (pintype "passive"))
      (node (ref "D1") (pin "C") (pinfunction "-_C") (pintype "passive"))
      (node (ref "HL1") (pin "9") (pinfunction "9_9") (pintype "bidirectional"))
      (node (ref "HL2") (pin "7") (pinfunction "7_7") (pintype "bidirectional"))
      (node (ref "HL4") (pin "4") (pinfunction "4_4") (pintype "bidirectional"))
      (node (ref "ICSP") (pin "6") (pinfunction "6_6") (pintype "bidirectional"))
      (node (ref "L1") (pin "1") (pinfunction "1_1") (pintype "passive"))
      (node (ref "OPAMP") (pin "8") (pinfunction "+V_8") (pintype "power_in"))
      (node (ref "Q1") (pin "2") (pinfunction "S_2") (pintype "passive"))
      (node (ref "R1") (pin "2") (pinfunction "2_2") (pintype "passive"))
      (node (ref "R10") (pin "1") (pinfunction "1_1") (pintype "passive"))
      (node (ref "R6") (pin "1") (pinfunction "1_1") (pintype "passive"))
      (node (ref "R9") (pin "1") (pinfunction "1_1") (pintype "passive"))
      (node (ref "SK0") (pin "4") (pinfunction "VDD_4") (pintype "bidirectional"))
      (node (ref "SK1") (pin "4") (pinfunction "VDD_4") (pintype "bidirectional"))
      (node (ref "SK10") (pin "4") (pinfunction "VDD_4") (pintype "bidirectional"))
      (node (ref "SK11") (pin "4") (pinfunction "VDD_4") (pintype "bidirectional"))
      (node (ref "SK12") (pin "4") (pinfunction "VDD_4") (pintype "bidirectional"))
      (node (ref "SK13") (pin "4") (pinfunction "VDD_4") (pintype "bidirectional"))
      (node (ref "SK14") (pin "4") (pinfunction "VDD_4") (pintype "bidirectional"))
      (node (ref "SK15") (pin "4") (pinfunction "VDD_4") (pintype "bidirectional"))
      (node (ref "SK2") (pin "4") (pinfunction "VDD_4") (pintype "bidirectional"))
      (node (ref "SK3") (pin "4") (pinfunction "VDD_4") (pintype "bidirectional"))
      (node (ref "SK4") (pin "4") (pinfunction "VDD_4") (pintype "bidirectional"))
      (node (ref "SK5") (pin "4") (pinfunction "VDD_4") (pintype "bidirectional"))
      (node (ref "SK6") (pin "4") (pinfunction "VDD_4") (pintype "bidirectional"))
      (node (ref "SK7") (pin "4") (pinfunction "VDD_4") (pintype "bidirectional"))
      (node (ref "SK8") (pin "4") (pinfunction "VDD_4") (pintype "bidirectional"))
      (node (ref "SK9") (pin "4") (pinfunction "VDD_4") (pintype "bidirectional"))
      (node (ref "UC") (pin "14") (pinfunction "VCC_14") (pintype "power_in"))
      (node (ref "UC") (pin "2") (pinfunction "UVCC_2") (pintype "power_in"))
      (node (ref "UC") (pin "34") (pinfunction "VCC_34") (pintype "power_in"))
      (node (ref "UMBRA") (pin "17") (pinfunction "17_17") (pintype "bidirectional"))
      (node (ref "UMBRA") (pin "18") (pinfunction "18_18") (pintype "bidirectional"))
      (node (ref "VR33") (pin "3") (pinfunction "VIN_3") (pintype "input"))
      (node (ref "VR50") (pin "2") (pinfunction "OUT_2") (pintype "bidirectional"))
      (node (ref "VR50") (pin "TER") (pinfunction "OUT_TER") (pintype "bidirectional"))
    )
    (net (code "72") (name "VIN") (class "Default")
      (node (ref "5-12V") (pin "1") (pinfunction "1_1") (pintype "passive"))
      (node (ref "C13") (pin "2") (pinfunction "2_2") (pintype "passive"))
      (node (ref "D5") (pin "2") (pinfunction "-_2") (pintype "passive"))
      (node (ref "HL4") (pin "2") (pinfunction "2_2") (pintype "bidirectional"))
      (node (ref "R11") (pin "2") (pinfunction "2_2") (pintype "passive"))
      (node (ref "VR50") (pin "3") (pinfunction "IN_3") (pintype "bidirectional"))
    )
    (net (code "73") (name "VUSB") (class "Default")
      (node (ref "C10") (pin "2") (pinfunction "2_2") (pintype "passive"))
      (node (ref "C11") (pin "2") (pinfunction "2_2") (pintype "passive"))
      (node (ref "L2") (pin "2") (pinfunction "2_2") (pintype "passive"))
      (node (ref "Q1") (pin "3") (pinfunction "D_3") (pintype "passive"))
      (node (ref "UC") (pin "7") (pinfunction "VBUS_7") (pintype "bidirectional"))
    )
  )
)
